# 3_2.net
KiCad netlist of a schematic drawn in Altium Designer
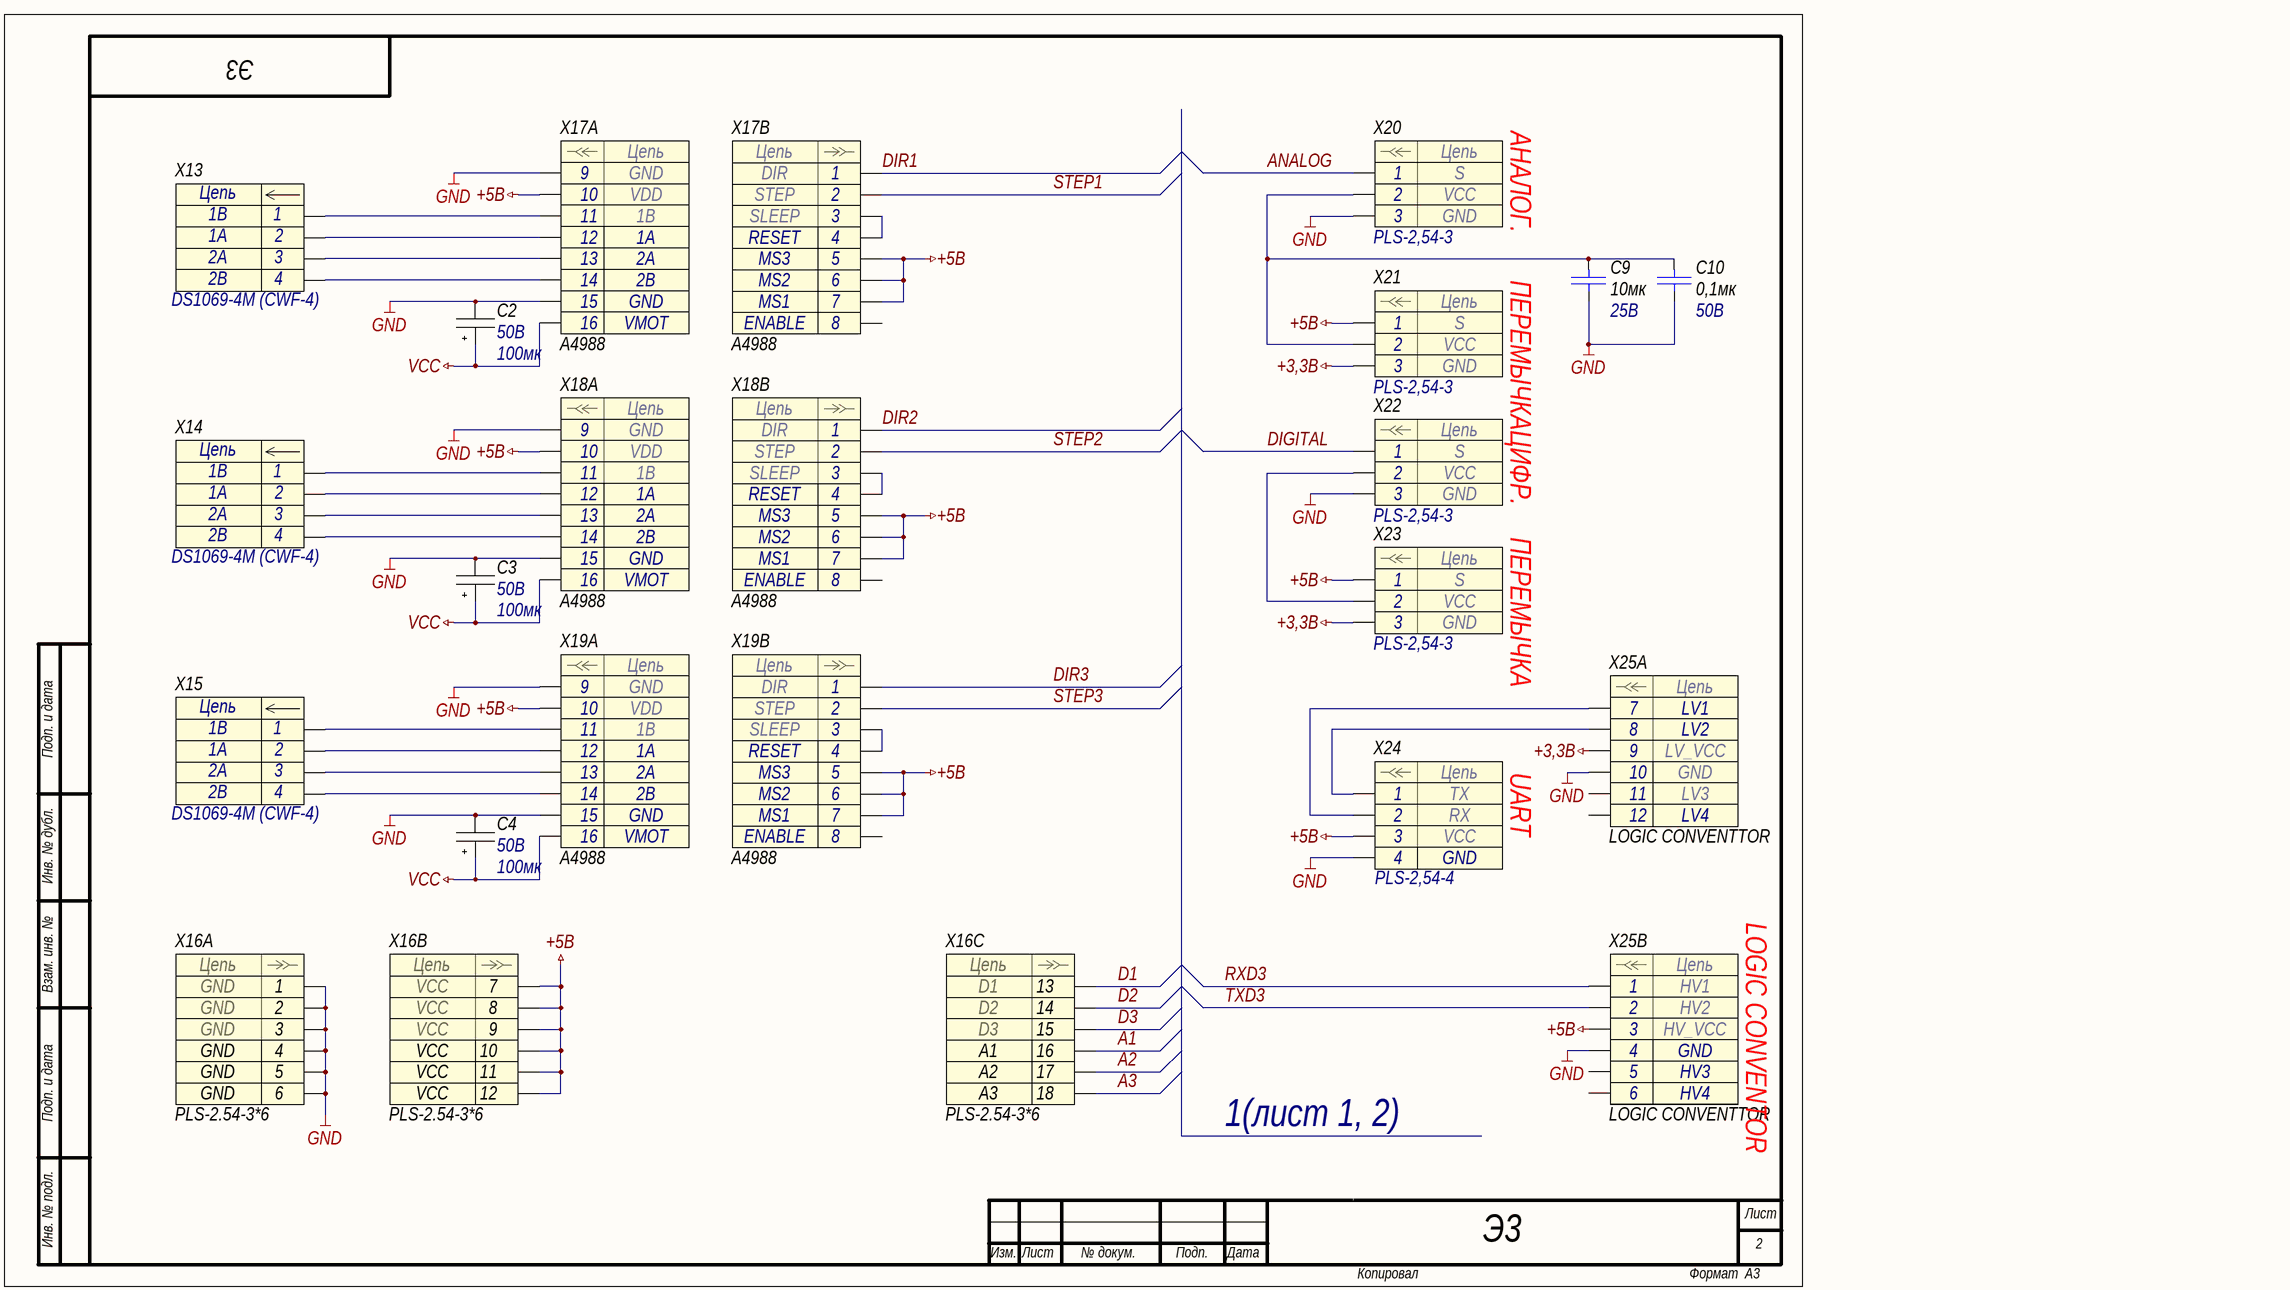
[diagram p0: Э3_2.SchDoc]

(export (version "E")
  (design (tool "Eeschema 10.0.6"))
  (components
    (comp (ref "C2")
      (value "конденсатор")
      (footprint "SK050M0100B3F-0811-up")
      (fields (field (name "VOLTAGE") "50В") (field (name "NOMINAL") "100мк"))
      (libsource (lib "LibraryPloshchadnaia") (part "SK050M0100B3F-0811"))
    )
    (comp (ref "C3")
      (value "конденсатор")
      (footprint "SK050M0100B3F-0811-up")
      (fields (field (name "VOLTAGE") "50В") (field (name "NOMINAL") "100мк"))
      (libsource (lib "LibraryPloshchadnaia") (part "SK050M0100B3F-0811"))
    )
    (comp (ref "C4")
      (value "конденсатор")
      (footprint "SK050M0100B3F-0811-up")
      (fields (field (name "VOLTAGE") "50В") (field (name "NOMINAL") "100мк"))
      (libsource (lib "LibraryPloshchadnaia") (part "SK050M0100B3F-0811"))
    )
    (comp (ref "C9")
      (value "10мк")
      (footprint "C1206")
      (description "Конденсатор кер. 10мкФ 25В")
      (fields (field (name "MANUFACTURER") "Yageo") (field (name "VOLTAGE") "25В"))
      (libsource (lib "capacitors") (part "CC1206KKX7R8BB106"))
    )
    (comp (ref "C10")
      (value "0,1мк")
      (footprint "C0603")
      (description "Конденсатор кер. 0,1мкФ 50В X7R")
      (fields (field (name "MANUFACTURER") "Murata") (field (name "VOLTAGE") "50В"))
      (libsource (lib "capacitors") (part "GRM188R71H104KA93D"))
    )
    (comp (ref "X13")
      (value "DS1069-4M (CWF-4)")
      (footprint "CWF-4")
      (description "Разъем - 4 конт. прямая вилка на плату")
      (fields (field (name "NAME") "DS1069-4M (CWF-4)"))
      (libsource (lib "headers") (part "CWF-4"))
    )
    (comp (ref "X14")
      (value "DS1069-4M (CWF-4)")
      (footprint "CWF-4")
      (description "Разъем - 4 конт. прямая вилка на плату")
      (fields (field (name "NAME") "DS1069-4M (CWF-4)"))
      (libsource (lib "headers") (part "CWF-4"))
    )
    (comp (ref "X15")
      (value "DS1069-4M (CWF-4)")
      (footprint "CWF-4")
      (description "Разъем - 4 конт. прямая вилка на плату")
      (fields (field (name "NAME") "DS1069-4M (CWF-4)"))
      (libsource (lib "headers") (part "CWF-4"))
    )
    (comp (ref "X16")
      (value "PLS-2.54-3*6")
      (footprint "PLS-2.54-3*6")
      (libsource (lib "LibraryPloshchadnaia") (part "PLS-2.54-3*6"))
    )
    (comp (ref "X17")
      (value "A4988")
      (footprint "A4988")
      (libsource (lib "LibraryPloshchadnaia") (part "A4988"))
    )
    (comp (ref "X18") (value "A4988") (footprint "A4988") (libsource (lib "") (part "A4988_1")))
    (comp (ref "X19") (value "A4988") (footprint "A4988") (libsource (lib "") (part "A4988_1")))
    (comp (ref "X20")
      (value "PLS-2,54-3")
      (footprint "PLS-2.54-3")
      (fields (field (name "NAM") "PLS-2,54-3"))
      (libsource (lib "LibraryPloshchadnaia") (part "PLS-2.54-3 1{gt}2"))
    )
    (comp (ref "X21")
      (value "PLS-2,54-3")
      (footprint "PLS-2.54-3")
      (fields (field (name "NAM") "PLS-2,54-3"))
      (libsource (lib "LibraryPloshchadnaia") (part "PLS-2.54-3 1{gt}2"))
    )
    (comp (ref "X22")
      (value "PLS-2,54-3")
      (footprint "PLS-2.54-3")
      (fields (field (name "NAM") "PLS-2,54-3"))
      (libsource (lib "LibraryPloshchadnaia") (part "PLS-2.54-3 1{gt}2"))
    )
    (comp (ref "X23")
      (value "PLS-2,54-3")
      (footprint "PLS-2.54-3")
      (fields (field (name "NAM") "PLS-2,54-3"))
      (libsource (lib "LibraryPloshchadnaia") (part "PLS-2.54-3 1{gt}2"))
    )
    (comp (ref "X24")
      (value "PLS-2,54-4")
      (footprint "PLS-2.54-4")
      (fields (field (name "NAM") "PLS-2,54-4"))
      (libsource (lib "LibraryPloshchadnaia") (part "PLS-2.54-4"))
    )
    (comp (ref "X25")
      (value "LOGIC CONVENTTOR")
      (footprint "LOGIC CONVENTOR")
      (libsource (lib "LibraryPloshchadnaia") (part "LOGIC CONVENTTOR"))
    )
  )
  (nets
    (net (code "1") (name "+3,3В") (class "Default")
      (node (ref "X21") (pin "3") (pinfunction "3_3") (pintype "passive"))
      (node (ref "X23") (pin "3") (pinfunction "3_3") (pintype "passive"))
      (node (ref "X25") (pin "9") (pinfunction "9_9") (pintype "passive"))
    )
    (net (code "2") (name "+5В") (class "Default")
      (node (ref "X16") (pin "10") (pinfunction "10_10") (pintype "passive"))
      (node (ref "X16") (pin "11") (pinfunction "11_11") (pintype "passive"))
      (node (ref "X16") (pin "12") (pinfunction "12_12") (pintype "passive"))
      (node (ref "X16") (pin "7") (pinfunction "7_7") (pintype "passive"))
      (node (ref "X16") (pin "8") (pinfunction "8_8") (pintype "passive"))
      (node (ref "X16") (pin "9") (pinfunction "9_9") (pintype "passive"))
      (node (ref "X17") (pin "10") (pinfunction "10_10") (pintype "passive"))
      (node (ref "X17") (pin "5") (pinfunction "5_5") (pintype "passive"))
      (node (ref "X17") (pin "6") (pinfunction "6_6") (pintype "passive"))
      (node (ref "X17") (pin "7") (pinfunction "7_7") (pintype "passive"))
      (node (ref "X18") (pin "10") (pinfunction "10_10") (pintype "passive"))
      (node (ref "X18") (pin "5") (pinfunction "5_5") (pintype "passive"))
      (node (ref "X18") (pin "6") (pinfunction "6_6") (pintype "passive"))
      (node (ref "X18") (pin "7") (pinfunction "7_7") (pintype "passive"))
      (node (ref "X19") (pin "10") (pinfunction "10_10") (pintype "passive"))
      (node (ref "X19") (pin "5") (pinfunction "5_5") (pintype "passive"))
      (node (ref "X19") (pin "6") (pinfunction "6_6") (pintype "passive"))
      (node (ref "X19") (pin "7") (pinfunction "7_7") (pintype "passive"))
      (node (ref "X21") (pin "1") (pinfunction "1_1") (pintype "passive"))
      (node (ref "X23") (pin "1") (pinfunction "1_1") (pintype "passive"))
      (node (ref "X24") (pin "3") (pinfunction "3_3") (pintype "passive"))
      (node (ref "X25") (pin "3") (pinfunction "3_3") (pintype "passive"))
    )
    (net (code "3") (name "/A1") (class "Default")
      (node (ref "X16") (pin "16") (pinfunction "16_16") (pintype "passive"))
    )
    (net (code "4") (name "/A2") (class "Default")
      (node (ref "X16") (pin "17") (pinfunction "17_17") (pintype "passive"))
    )
    (net (code "5") (name "/A3") (class "Default")
      (node (ref "X16") (pin "18") (pinfunction "18_18") (pintype "passive"))
    )
    (net (code "6") (name "/ANALOG") (class "Default")
      (node (ref "X20") (pin "1") (pinfunction "1_1") (pintype "passive"))
    )
    (net (code "7") (name "/D1") (class "Default")
      (node (ref "X16") (pin "13") (pinfunction "13_13") (pintype "passive"))
    )
    (net (code "8") (name "/D2") (class "Default")
      (node (ref "X16") (pin "14") (pinfunction "14_14") (pintype "passive"))
    )
    (net (code "9") (name "/D3") (class "Default")
      (node (ref "X16") (pin "15") (pinfunction "15_15") (pintype "passive"))
    )
    (net (code "10") (name "/DIGITAL") (class "Default")
      (node (ref "X22") (pin "1") (pinfunction "1_1") (pintype "passive"))
    )
    (net (code "11") (name "/DIR1") (class "Default")
      (node (ref "X17") (pin "1") (pinfunction "1_1") (pintype "passive"))
    )
    (net (code "12") (name "/DIR2") (class "Default")
      (node (ref "X18") (pin "1") (pinfunction "1_1") (pintype "passive"))
    )
    (net (code "13") (name "/DIR3") (class "Default")
      (node (ref "X19") (pin "1") (pinfunction "1_1") (pintype "passive"))
    )
    (net (code "14") (name "/RXD3") (class "Default")
      (node (ref "X25") (pin "1") (pinfunction "1_1") (pintype "passive"))
    )
    (net (code "15") (name "/STEP1") (class "Default")
      (node (ref "X17") (pin "2") (pinfunction "2_2") (pintype "passive"))
    )
    (net (code "16") (name "/STEP2") (class "Default")
      (node (ref "X18") (pin "2") (pinfunction "2_2") (pintype "passive"))
    )
    (net (code "17") (name "/STEP3") (class "Default")
      (node (ref "X19") (pin "2") (pinfunction "2_2") (pintype "passive"))
    )
    (net (code "18") (name "/TXD3") (class "Default")
      (node (ref "X25") (pin "2") (pinfunction "2_2") (pintype "passive"))
    )
    (net (code "19") (name "GND") (class "Default")
      (node (ref "C10") (pin "1") (pinfunction "1_1") (pintype "passive"))
      (node (ref "C2") (pin "2") (pinfunction "2_2") (pintype "passive"))
      (node (ref "C3") (pin "2") (pinfunction "2_2") (pintype "passive"))
      (node (ref "C4") (pin "2") (pinfunction "2_2") (pintype "passive"))
      (node (ref "C9") (pin "1") (pinfunction "1_1") (pintype "passive"))
      (node (ref "X16") (pin "1") (pinfunction "1_1") (pintype "passive"))
      (node (ref "X16") (pin "2") (pinfunction "2_2") (pintype "passive"))
      (node (ref "X16") (pin "3") (pinfunction "3_3") (pintype "passive"))
      (node (ref "X16") (pin "4") (pinfunction "4_4") (pintype "passive"))
      (node (ref "X16") (pin "5") (pinfunction "5_5") (pintype "passive"))
      (node (ref "X16") (pin "6") (pinfunction "6_6") (pintype "passive"))
      (node (ref "X17") (pin "15") (pinfunction "15_15") (pintype "passive"))
      (node (ref "X17") (pin "9") (pinfunction "9_9") (pintype "passive"))
      (node (ref "X18") (pin "15") (pinfunction "15_15") (pintype "passive"))
      (node (ref "X18") (pin "9") (pinfunction "9_9") (pintype "passive"))
      (node (ref "X19") (pin "15") (pinfunction "15_15") (pintype "passive"))
      (node (ref "X19") (pin "9") (pinfunction "9_9") (pintype "passive"))
      (node (ref "X20") (pin "3") (pinfunction "3_3") (pintype "passive"))
      (node (ref "X22") (pin "3") (pinfunction "3_3") (pintype "passive"))
      (node (ref "X24") (pin "4") (pinfunction "4_4") (pintype "passive"))
      (node (ref "X25") (pin "10") (pinfunction "10_10") (pintype "passive"))
      (node (ref "X25") (pin "4") (pinfunction "4_4") (pintype "passive"))
    )
    (net (code "20") (name "Net-(C10-Pad2)") (class "Default")
      (node (ref "C10") (pin "2") (pinfunction "2_2") (pintype "passive"))
      (node (ref "C9") (pin "2") (pinfunction "2_2") (pintype "passive"))
      (node (ref "X20") (pin "2") (pinfunction "2_2") (pintype "passive"))
      (node (ref "X21") (pin "2") (pinfunction "2_2") (pintype "passive"))
    )
    (net (code "21") (name "Net-(X13-Pad1)") (class "Default")
      (node (ref "X13") (pin "1") (pinfunction "1_1") (pintype "passive"))
      (node (ref "X17") (pin "11") (pinfunction "11_11") (pintype "passive"))
    )
    (net (code "22") (name "Net-(X13-Pad2)") (class "Default")
      (node (ref "X13") (pin "2") (pinfunction "2_2") (pintype "passive"))
      (node (ref "X17") (pin "12") (pinfunction "12_12") (pintype "passive"))
    )
    (net (code "23") (name "Net-(X13-Pad3)") (class "Default")
      (node (ref "X13") (pin "3") (pinfunction "3_3") (pintype "passive"))
      (node (ref "X17") (pin "13") (pinfunction "13_13") (pintype "passive"))
    )
    (net (code "24") (name "Net-(X13-Pad4)") (class "Default")
      (node (ref "X13") (pin "4") (pinfunction "4_4") (pintype "passive"))
      (node (ref "X17") (pin "14") (pinfunction "14_14") (pintype "passive"))
    )
    (net (code "25") (name "Net-(X14-Pad1)") (class "Default")
      (node (ref "X14") (pin "1") (pinfunction "1_1") (pintype "passive"))
      (node (ref "X18") (pin "11") (pinfunction "11_11") (pintype "passive"))
    )
    (net (code "26") (name "Net-(X14-Pad2)") (class "Default")
      (node (ref "X14") (pin "2") (pinfunction "2_2") (pintype "passive"))
      (node (ref "X18") (pin "12") (pinfunction "12_12") (pintype "passive"))
    )
    (net (code "27") (name "Net-(X14-Pad3)") (class "Default")
      (node (ref "X14") (pin "3") (pinfunction "3_3") (pintype "passive"))
      (node (ref "X18") (pin "13") (pinfunction "13_13") (pintype "passive"))
    )
    (net (code "28") (name "Net-(X14-Pad4)") (class "Default")
      (node (ref "X14") (pin "4") (pinfunction "4_4") (pintype "passive"))
      (node (ref "X18") (pin "14") (pinfunction "14_14") (pintype "passive"))
    )
    (net (code "29") (name "Net-(X15-Pad1)") (class "Default")
      (node (ref "X15") (pin "1") (pinfunction "1_1") (pintype "passive"))
      (node (ref "X19") (pin "11") (pinfunction "11_11") (pintype "passive"))
    )
    (net (code "30") (name "Net-(X15-Pad2)") (class "Default")
      (node (ref "X15") (pin "2") (pinfunction "2_2") (pintype "passive"))
      (node (ref "X19") (pin "12") (pinfunction "12_12") (pintype "passive"))
    )
    (net (code "31") (name "Net-(X15-Pad3)") (class "Default")
      (node (ref "X15") (pin "3") (pinfunction "3_3") (pintype "passive"))
      (node (ref "X19") (pin "13") (pinfunction "13_13") (pintype "passive"))
    )
    (net (code "32") (name "Net-(X15-Pad4)") (class "Default")
      (node (ref "X15") (pin "4") (pinfunction "4_4") (pintype "passive"))
      (node (ref "X19") (pin "14") (pinfunction "14_14") (pintype "passive"))
    )
    (net (code "33") (name "Net-(X17-Pad3)") (class "Default")
      (node (ref "X17") (pin "3") (pinfunction "3_3") (pintype "passive"))
      (node (ref "X17") (pin "4") (pinfunction "4_4") (pintype "passive"))
    )
    (net (code "34") (name "Net-(X18-Pad3)") (class "Default")
      (node (ref "X18") (pin "3") (pinfunction "3_3") (pintype "passive"))
      (node (ref "X18") (pin "4") (pinfunction "4_4") (pintype "passive"))
    )
    (net (code "35") (name "Net-(X19-Pad3)") (class "Default")
      (node (ref "X19") (pin "3") (pinfunction "3_3") (pintype "passive"))
      (node (ref "X19") (pin "4") (pinfunction "4_4") (pintype "passive"))
    )
    (net (code "36") (name "Net-(X22-Pad2)") (class "Default")
      (node (ref "X22") (pin "2") (pinfunction "2_2") (pintype "passive"))
      (node (ref "X23") (pin "2") (pinfunction "2_2") (pintype "passive"))
    )
    (net (code "37") (name "Net-(X24-Pad1)") (class "Default")
      (node (ref "X24") (pin "1") (pinfunction "1_1") (pintype "passive"))
      (node (ref "X25") (pin "8") (pinfunction "8_8") (pintype "passive"))
    )
    (net (code "38") (name "Net-(X24-Pad2)") (class "Default")
      (node (ref "X24") (pin "2") (pinfunction "2_2") (pintype "passive"))
      (node (ref "X25") (pin "7") (pinfunction "7_7") (pintype "passive"))
    )
    (net (code "39") (name "VCC") (class "Default")
      (node (ref "C2") (pin "1") (pinfunction "1_1") (pintype "passive"))
      (node (ref "C3") (pin "1") (pinfunction "1_1") (pintype "passive"))
      (node (ref "C4") (pin "1") (pinfunction "1_1") (pintype "passive"))
      (node (ref "X17") (pin "16") (pinfunction "16_16") (pintype "passive"))
      (node (ref "X18") (pin "16") (pinfunction "16_16") (pintype "passive"))
      (node (ref "X19") (pin "16") (pinfunction "16_16") (pintype "passive"))
    )
    (net (code "40") (name "unconnected-(X17-Pad8)") (class "Default")
      (node (ref "X17") (pin "8") (pinfunction "8_8") (pintype "passive"))
    )
    (net (code "41") (name "unconnected-(X18-Pad8)") (class "Default")
      (node (ref "X18") (pin "8") (pinfunction "8_8") (pintype "passive"))
    )
    (net (code "42") (name "unconnected-(X19-Pad8)") (class "Default")
      (node (ref "X19") (pin "8") (pinfunction "8_8") (pintype "passive"))
    )
    (net (code "43") (name "unconnected-(X25-Pad5)") (class "Default")
      (node (ref "X25") (pin "5") (pinfunction "5_5") (pintype "passive"))
    )
    (net (code "44") (name "unconnected-(X25-Pad6)") (class "Default")
      (node (ref "X25") (pin "6") (pinfunction "6_6") (pintype "passive"))
    )
    (net (code "45") (name "unconnected-(X25-Pad11)") (class "Default")
      (node (ref "X25") (pin "11") (pinfunction "11_11") (pintype "passive"))
    )
    (net (code "46") (name "unconnected-(X25-Pad12)") (class "Default")
      (node (ref "X25") (pin "12") (pinfunction "12_12") (pintype "passive"))
    )
  )
)
